# main.net
KiCad netlist of a schematic drawn in EAGLE
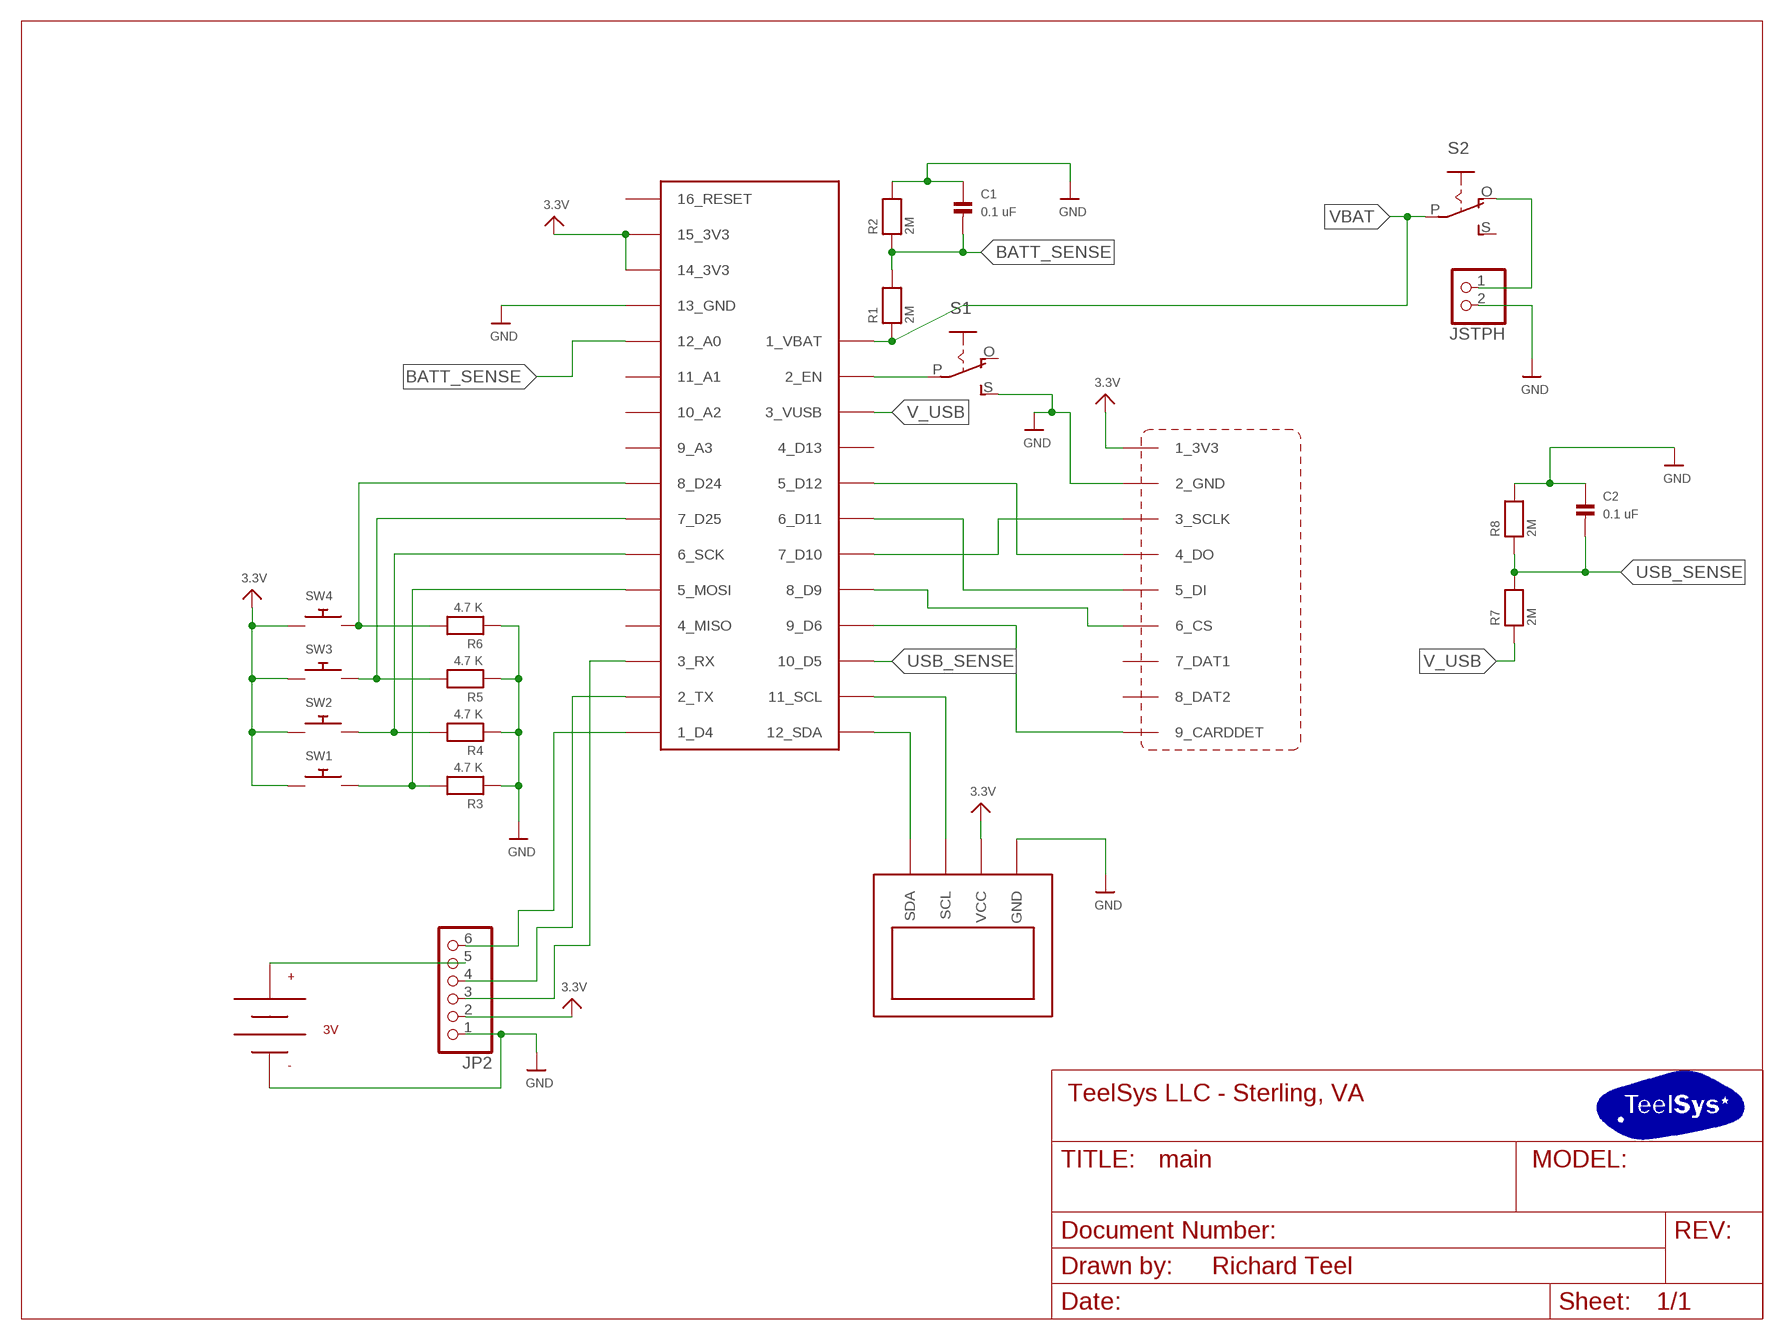
[diagram p0: schematic, sheet 1]

(export (version "E")
  (design (tool "Eeschema 10.0.6"))
  (components
    (comp (ref "BAT_1")
      (value "CR2032_HOLDER_WMYCONGCONG")
      (footprint "eagle-import:CR2032_HOLDER_WMYCONGCONG")
      (libsource (lib "eagle-import") (part "CR2032_HOLDER_WMYCONGCONG"))
    )
    (comp (ref "C1")
      (value "0.1 uF")
      (footprint "eagle-import:_0805")
      (libsource (lib "eagle-import") (part "CAP_CERAMIC_0805"))
    )
    (comp (ref "C2")
      (value "0.1 uF")
      (footprint "eagle-import:_0805")
      (libsource (lib "eagle-import") (part "CAP_CERAMIC_0805"))
    )
    (comp (ref "FEATHER_RP2040")
      (value "ADAFRUIT_FEATHER_RP2040")
      (footprint "eagle-import:ADAFRUIT_FEATHER")
      (libsource (lib "eagle-import") (part "ADAFRUIT_FEATHER_RP2040"))
    )
    (comp (ref "JP2")
      (value "HEADER-1X6ROUND")
      (footprint "eagle-import:1X06_ROUND")
      (libsource (lib "eagle-import") (part "HEADER-1X6ROUND"))
    )
    (comp (ref "JSTPH")
      (value "JST_2PIN-SMT-RA")
      (footprint "eagle-import:JST-PH-2-SMT-RA")
      (libsource (lib "eagle-import") (part "JST_2PIN-SMT-RA"))
    )
    (comp (ref "R1")
      (value "2M")
      (footprint "eagle-import:0805")
      (libsource (lib "eagle-import") (part "RESISTOR0805"))
    )
    (comp (ref "R2")
      (value "2M")
      (footprint "eagle-import:0805")
      (libsource (lib "eagle-import") (part "RESISTOR0805"))
    )
    (comp (ref "R3")
      (value "4.7 K")
      (footprint "eagle-import:0805")
      (libsource (lib "eagle-import") (part "RESISTOR0805"))
    )
    (comp (ref "R4")
      (value "4.7 K")
      (footprint "eagle-import:0805")
      (libsource (lib "eagle-import") (part "RESISTOR0805"))
    )
    (comp (ref "R5")
      (value "4.7 K")
      (footprint "eagle-import:0805")
      (libsource (lib "eagle-import") (part "RESISTOR0805"))
    )
    (comp (ref "R6")
      (value "4.7 K")
      (footprint "eagle-import:0805")
      (libsource (lib "eagle-import") (part "RESISTOR0805"))
    )
    (comp (ref "R7")
      (value "2M")
      (footprint "eagle-import:0805")
      (libsource (lib "eagle-import") (part "RESISTOR0805"))
    )
    (comp (ref "R8")
      (value "2M")
      (footprint "eagle-import:0805")
      (libsource (lib "eagle-import") (part "RESISTOR0805"))
    )
    (comp (ref "S1")
      (value "EG1218S")
      (footprint "eagle-import:EG1218")
      (libsource (lib "eagle-import") (part "EG1218S"))
    )
    (comp (ref "S2")
      (value "EG1218S")
      (footprint "eagle-import:EG1218")
      (libsource (lib "eagle-import") (part "EG1218S"))
    )
    (comp (ref "SDCARD2")
      (value "ADAFRUIT_SDCARD3V3BOTTOM_MNT")
      (footprint "eagle-import:ADAFRUIT_SDCARD3V3_B")
      (libsource (lib "eagle-import") (part "ADAFRUIT_SDCARD3V3BOTTOM_MNT"))
    )
    (comp (ref "SW1")
      (value "SWITCH_PUSHBUTTONEVQ-PE")
      (footprint "eagle-import:TACT_PANA-EVQ")
      (libsource (lib "eagle-import") (part "SWITCH_PUSHBUTTONEVQ-PE"))
    )
    (comp (ref "SW2")
      (value "SWITCH_PUSHBUTTONEVQ-PE")
      (footprint "eagle-import:TACT_PANA-EVQ")
      (libsource (lib "eagle-import") (part "SWITCH_PUSHBUTTONEVQ-PE"))
    )
    (comp (ref "SW3")
      (value "SWITCH_PUSHBUTTONEVQ-PE")
      (footprint "eagle-import:TACT_PANA-EVQ")
      (libsource (lib "eagle-import") (part "SWITCH_PUSHBUTTONEVQ-PE"))
    )
    (comp (ref "SW4")
      (value "SWITCH_PUSHBUTTONEVQ-PE")
      (footprint "eagle-import:TACT_PANA-EVQ")
      (libsource (lib "eagle-import") (part "SWITCH_PUSHBUTTONEVQ-PE"))
    )
    (comp (ref "U$10")
      (value "OLED_SDD1306_128X64FRIENDA")
      (footprint "eagle-import:OLED_SDD1306_128X64")
      (libsource (lib "eagle-import") (part "OLED_SDD1306_128X64FRIENDA"))
    )
  )
  (nets
    (net (code "1") (name "3.3V") (class "Default")
      (node (ref "FEATHER_RP2040") (pin "14_3V3") (pinfunction "14_3V3_14_3V3") (pintype "bidirectional"))
      (node (ref "FEATHER_RP2040") (pin "15_3V3") (pinfunction "15_3V3_15_3V3") (pintype "bidirectional"))
      (node (ref "JP2") (pin "2") (pinfunction "2_2") (pintype "passive"))
      (node (ref "SDCARD2") (pin "1_3V3") (pinfunction "1_3V3_1_3V3") (pintype "bidirectional"))
      (node (ref "SW1") (pin "P$1") (pinfunction "P$1_P$1") (pintype "passive"))
      (node (ref "SW2") (pin "P$1") (pinfunction "P$1_P$1") (pintype "passive"))
      (node (ref "SW3") (pin "P$1") (pinfunction "P$1_P$1") (pintype "passive"))
      (node (ref "SW4") (pin "P$1") (pinfunction "P$1_P$1") (pintype "passive"))
      (node (ref "U$10") (pin "2_VCC") (pinfunction "VCC_2_VCC") (pintype "bidirectional"))
    )
    (net (code "2") (name "BATT_SENSE") (class "Default")
      (node (ref "C1") (pin "2") (pinfunction "P$2_2") (pintype "passive"))
      (node (ref "FEATHER_RP2040") (pin "12_A0") (pinfunction "12_A0_12_A0") (pintype "bidirectional"))
      (node (ref "R1") (pin "2") (pinfunction "2_2") (pintype "passive"))
      (node (ref "R2") (pin "1") (pinfunction "1_1") (pintype "passive"))
    )
    (net (code "3") (name "GND") (class "Default")
      (node (ref "BAT_1") (pin "V-") (pinfunction "-_V-") (pintype "bidirectional"))
      (node (ref "C1") (pin "1") (pinfunction "P$1_1") (pintype "passive"))
      (node (ref "C2") (pin "1") (pinfunction "P$1_1") (pintype "passive"))
      (node (ref "FEATHER_RP2040") (pin "13_GND") (pinfunction "13_GND_13_GND") (pintype "bidirectional"))
      (node (ref "JP2") (pin "1") (pinfunction "1_1") (pintype "passive"))
      (node (ref "JSTPH") (pin "2") (pinfunction "1_2") (pintype "passive"))
      (node (ref "R2") (pin "2") (pinfunction "2_2") (pintype "passive"))
      (node (ref "R3") (pin "1") (pinfunction "1_1") (pintype "passive"))
      (node (ref "R4") (pin "1") (pinfunction "1_1") (pintype "passive"))
      (node (ref "R5") (pin "1") (pinfunction "1_1") (pintype "passive"))
      (node (ref "R6") (pin "1") (pinfunction "1_1") (pintype "passive"))
      (node (ref "R8") (pin "2") (pinfunction "2_2") (pintype "passive"))
      (node (ref "S1") (pin "S") (pinfunction "S_S") (pintype "passive"))
      (node (ref "SDCARD2") (pin "2_GND") (pinfunction "2_GND_2_GND") (pintype "bidirectional"))
      (node (ref "U$10") (pin "1_GND") (pinfunction "GND_1_GND") (pintype "bidirectional"))
    )
    (net (code "4") (name "Net-(BAT_1-+)") (class "Default")
      (node (ref "BAT_1") (pin "V+") (pinfunction "+_V+") (pintype "bidirectional"))
      (node (ref "JP2") (pin "5") (pinfunction "5_5") (pintype "passive"))
    )
    (net (code "5") (name "Net-(FEATHER_RP2040-Pad1_D4)") (class "Default")
      (node (ref "FEATHER_RP2040") (pin "1_D4") (pinfunction "1_D4_1_D4") (pintype "bidirectional"))
      (node (ref "JP2") (pin "6") (pinfunction "6_6") (pintype "passive"))
    )
    (net (code "6") (name "Net-(FEATHER_RP2040-Pad2_EN)") (class "Default")
      (node (ref "FEATHER_RP2040") (pin "2_EN") (pinfunction "2_EN_2_EN") (pintype "bidirectional"))
      (node (ref "S1") (pin "P") (pinfunction "P_P") (pintype "passive"))
    )
    (net (code "7") (name "Net-(FEATHER_RP2040-Pad2_TX)") (class "Default")
      (node (ref "FEATHER_RP2040") (pin "2_TX") (pinfunction "2_TX_2_TX") (pintype "bidirectional"))
      (node (ref "JP2") (pin "4") (pinfunction "4_4") (pintype "passive"))
    )
    (net (code "8") (name "Net-(FEATHER_RP2040-Pad3_RX)") (class "Default")
      (node (ref "FEATHER_RP2040") (pin "3_RX") (pinfunction "3_RX_3_RX") (pintype "bidirectional"))
      (node (ref "JP2") (pin "3") (pinfunction "3_3") (pintype "passive"))
    )
    (net (code "9") (name "Net-(FEATHER_RP2040-Pad5_D12)") (class "Default")
      (node (ref "FEATHER_RP2040") (pin "5_D12") (pinfunction "5_D12_5_D12") (pintype "bidirectional"))
      (node (ref "SDCARD2") (pin "4_DO") (pinfunction "4_DO_4_DO") (pintype "bidirectional"))
    )
    (net (code "10") (name "Net-(FEATHER_RP2040-Pad5_MOSI)") (class "Default")
      (node (ref "FEATHER_RP2040") (pin "5_MOSI") (pinfunction "5_MOSI_5_MOSI") (pintype "bidirectional"))
      (node (ref "R3") (pin "2") (pinfunction "2_2") (pintype "passive"))
      (node (ref "SW1") (pin "P$2") (pinfunction "P$2_P$2") (pintype "passive"))
    )
    (net (code "11") (name "Net-(FEATHER_RP2040-Pad6_D11)") (class "Default")
      (node (ref "FEATHER_RP2040") (pin "6_D11") (pinfunction "6_D11_6_D11") (pintype "bidirectional"))
      (node (ref "SDCARD2") (pin "5_DI") (pinfunction "5_DI_5_DI") (pintype "bidirectional"))
    )
    (net (code "12") (name "Net-(FEATHER_RP2040-Pad6_SCK)") (class "Default")
      (node (ref "FEATHER_RP2040") (pin "6_SCK") (pinfunction "6_SCK_6_SCK") (pintype "bidirectional"))
      (node (ref "R4") (pin "2") (pinfunction "2_2") (pintype "passive"))
      (node (ref "SW2") (pin "P$2") (pinfunction "P$2_P$2") (pintype "passive"))
    )
    (net (code "13") (name "Net-(FEATHER_RP2040-Pad7_D10)") (class "Default")
      (node (ref "FEATHER_RP2040") (pin "7_D10") (pinfunction "7_D10_7_D10") (pintype "bidirectional"))
      (node (ref "SDCARD2") (pin "3_SCLK") (pinfunction "3_SCLK_3_SCLK") (pintype "bidirectional"))
    )
    (net (code "14") (name "Net-(FEATHER_RP2040-Pad7_D25)") (class "Default")
      (node (ref "FEATHER_RP2040") (pin "7_D25") (pinfunction "7_D25_7_D25") (pintype "bidirectional"))
      (node (ref "R5") (pin "2") (pinfunction "2_2") (pintype "passive"))
      (node (ref "SW3") (pin "P$2") (pinfunction "P$2_P$2") (pintype "passive"))
    )
    (net (code "15") (name "Net-(FEATHER_RP2040-Pad8_D9)") (class "Default")
      (node (ref "FEATHER_RP2040") (pin "8_D9") (pinfunction "8_D9_8_D9") (pintype "bidirectional"))
      (node (ref "SDCARD2") (pin "6_CS") (pinfunction "6_CS_6_CS") (pintype "bidirectional"))
    )
    (net (code "16") (name "Net-(FEATHER_RP2040-Pad8_D24)") (class "Default")
      (node (ref "FEATHER_RP2040") (pin "8_D24") (pinfunction "8_D24_8_D24") (pintype "bidirectional"))
      (node (ref "R6") (pin "2") (pinfunction "2_2") (pintype "passive"))
      (node (ref "SW4") (pin "P$2") (pinfunction "P$2_P$2") (pintype "passive"))
    )
    (net (code "17") (name "Net-(FEATHER_RP2040-Pad9_D6)") (class "Default")
      (node (ref "FEATHER_RP2040") (pin "9_D6") (pinfunction "9_D6_9_D6") (pintype "bidirectional"))
      (node (ref "SDCARD2") (pin "9_CARDDET") (pinfunction "9_CARDDET_9_CARDDET") (pintype "bidirectional"))
    )
    (net (code "18") (name "Net-(JSTPH-2)") (class "Default")
      (node (ref "JSTPH") (pin "1") (pinfunction "2_1") (pintype "passive"))
      (node (ref "S2") (pin "O") (pinfunction "O_O") (pintype "passive"))
    )
    (net (code "19") (name "Net-(U$10-SCL)") (class "Default")
      (node (ref "FEATHER_RP2040") (pin "11_SCL") (pinfunction "11_SCL_11_SCL") (pintype "bidirectional"))
      (node (ref "U$10") (pin "3_SCL") (pinfunction "SCL_3_SCL") (pintype "bidirectional"))
    )
    (net (code "20") (name "Net-(U$10-SDA)") (class "Default")
      (node (ref "FEATHER_RP2040") (pin "12_SDA") (pinfunction "12_SDA_12_SDA") (pintype "bidirectional"))
      (node (ref "U$10") (pin "4_SDA") (pinfunction "SDA_4_SDA") (pintype "bidirectional"))
    )
    (net (code "21") (name "USB_SENSE") (class "Default")
      (node (ref "C2") (pin "2") (pinfunction "P$2_2") (pintype "passive"))
      (node (ref "FEATHER_RP2040") (pin "10_D5") (pinfunction "10_D5_10_D5") (pintype "bidirectional"))
      (node (ref "R7") (pin "2") (pinfunction "2_2") (pintype "passive"))
      (node (ref "R8") (pin "1") (pinfunction "1_1") (pintype "passive"))
    )
    (net (code "22") (name "VBAT") (class "Default")
      (node (ref "FEATHER_RP2040") (pin "1_VBAT") (pinfunction "1_VBAT_1_VBAT") (pintype "bidirectional"))
      (node (ref "R1") (pin "1") (pinfunction "1_1") (pintype "passive"))
      (node (ref "S2") (pin "P") (pinfunction "P_P") (pintype "passive"))
    )
    (net (code "23") (name "V_USB") (class "Default")
      (node (ref "FEATHER_RP2040") (pin "3_VBUS") (pinfunction "3_VUSB_3_VBUS") (pintype "bidirectional"))
      (node (ref "R7") (pin "1") (pinfunction "1_1") (pintype "passive"))
    )
    (net (code "24") (name "unconnected-(FEATHER_RP2040-Pad4_D13)") (class "Default")
      (node (ref "FEATHER_RP2040") (pin "4_D13") (pinfunction "4_D13_4_D13") (pintype "bidirectional"))
    )
    (net (code "25") (name "unconnected-(FEATHER_RP2040-Pad4_MISO)") (class "Default")
      (node (ref "FEATHER_RP2040") (pin "4_MISO") (pinfunction "4_MISO_4_MISO") (pintype "bidirectional"))
    )
    (net (code "26") (name "unconnected-(FEATHER_RP2040-Pad9_A3)") (class "Default")
      (node (ref "FEATHER_RP2040") (pin "9_A3") (pinfunction "9_A3_9_A3") (pintype "bidirectional"))
    )
    (net (code "27") (name "unconnected-(FEATHER_RP2040-Pad10_A2)") (class "Default")
      (node (ref "FEATHER_RP2040") (pin "10_A2") (pinfunction "10_A2_10_A2") (pintype "bidirectional"))
    )
    (net (code "28") (name "unconnected-(FEATHER_RP2040-Pad11_A1)") (class "Default")
      (node (ref "FEATHER_RP2040") (pin "11_A1") (pinfunction "11_A1_11_A1") (pintype "bidirectional"))
    )
    (net (code "29") (name "unconnected-(FEATHER_RP2040-Pad16_RESET)") (class "Default")
      (node (ref "FEATHER_RP2040") (pin "16_RESET") (pinfunction "16_RESET_16_RESET") (pintype "bidirectional"))
    )
    (net (code "30") (name "unconnected-(S1-PadO)") (class "Default")
      (node (ref "S1") (pin "O") (pinfunction "O_O") (pintype "passive"))
    )
    (net (code "31") (name "unconnected-(S2-PadS)") (class "Default")
      (node (ref "S2") (pin "S") (pinfunction "S_S") (pintype "passive"))
    )
    (net (code "32") (name "unconnected-(SDCARD2-Pad7_DAT1)") (class "Default")
      (node (ref "SDCARD2") (pin "7_DAT1") (pinfunction "7_DAT1_7_DAT1") (pintype "bidirectional"))
    )
    (net (code "33") (name "unconnected-(SDCARD2-Pad8_DAT2)") (class "Default")
      (node (ref "SDCARD2") (pin "8_DAT2") (pinfunction "8_DAT2_8_DAT2") (pintype "bidirectional"))
    )
  )
)
